# top_schem_rev3.net
KiCad netlist of a schematic drawn in Altium Designer
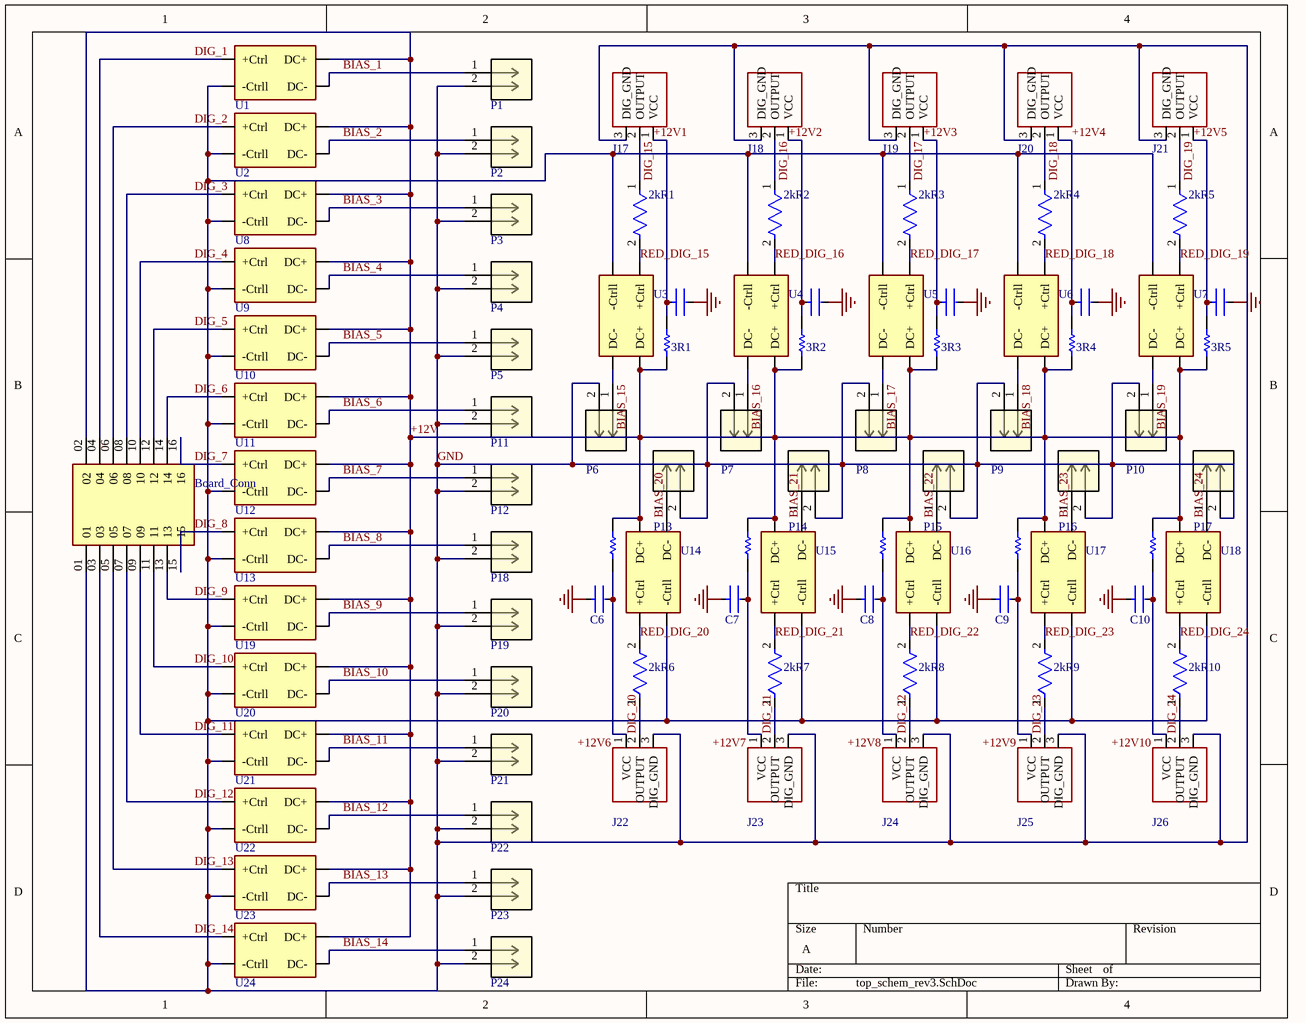
[diagram p0: top_schem_rev3.SchDoc]

(export (version "E")
  (design (tool "Eeschema 10.0.6"))
  (components
    (comp (ref "2kR1")
      (value "CRCW06031K80FKEA")
      (footprint "2kOhm")
      (description "Res Thick Film 0603 1.8K Ohm 1% 1/10W ±100ppm/°C Molded SMD Paper T/R")
      (fields (field (name "MANUFACTURER") "Vishay") (field (name "TOLERANCE") "1%"))
      (libsource (lib "ps_schlib") (part "CRCW06031K80FKEA"))
    )
    (comp (ref "2kR2")
      (value "CRCW06031K80FKEA")
      (footprint "2kOhm")
      (description "Res Thick Film 0603 1.8K Ohm 1% 1/10W ±100ppm/°C Molded SMD Paper T/R")
      (fields (field (name "MANUFACTURER") "Vishay") (field (name "TOLERANCE") "1%"))
      (libsource (lib "ps_schlib") (part "CRCW06031K80FKEA"))
    )
    (comp (ref "2kR3")
      (value "CRCW06031K80FKEA")
      (footprint "2kOhm")
      (description "Res Thick Film 0603 1.8K Ohm 1% 1/10W ±100ppm/°C Molded SMD Paper T/R")
      (fields (field (name "MANUFACTURER") "Vishay") (field (name "TOLERANCE") "1%"))
      (libsource (lib "ps_schlib") (part "CRCW06031K80FKEA"))
    )
    (comp (ref "2kR4")
      (value "CRCW06031K80FKEA")
      (footprint "2kOhm")
      (description "Res Thick Film 0603 1.8K Ohm 1% 1/10W ±100ppm/°C Molded SMD Paper T/R")
      (fields (field (name "MANUFACTURER") "Vishay") (field (name "TOLERANCE") "1%"))
      (libsource (lib "ps_schlib") (part "CRCW06031K80FKEA"))
    )
    (comp (ref "2kR5")
      (value "CRCW06031K80FKEA")
      (footprint "2kOhm")
      (description "Res Thick Film 0603 1.8K Ohm 1% 1/10W ±100ppm/°C Molded SMD Paper T/R")
      (fields (field (name "MANUFACTURER") "Vishay") (field (name "TOLERANCE") "1%"))
      (libsource (lib "ps_schlib") (part "CRCW06031K80FKEA"))
    )
    (comp (ref "2kR6")
      (value "CRCW06031K80FKEA")
      (footprint "2kOhm")
      (description "Res Thick Film 0603 1.8K Ohm 1% 1/10W ±100ppm/°C Molded SMD Paper T/R")
      (fields (field (name "MANUFACTURER") "Vishay") (field (name "TOLERANCE") "1%"))
      (libsource (lib "ps_schlib") (part "CRCW06031K80FKEA"))
    )
    (comp (ref "2kR7")
      (value "CRCW06031K80FKEA")
      (footprint "2kOhm")
      (description "Res Thick Film 0603 1.8K Ohm 1% 1/10W ±100ppm/°C Molded SMD Paper T/R")
      (fields (field (name "MANUFACTURER") "Vishay") (field (name "TOLERANCE") "1%"))
      (libsource (lib "ps_schlib") (part "CRCW06031K80FKEA"))
    )
    (comp (ref "2kR8")
      (value "CRCW06031K80FKEA")
      (footprint "2kOhm")
      (description "Res Thick Film 0603 1.8K Ohm 1% 1/10W ±100ppm/°C Molded SMD Paper T/R")
      (fields (field (name "MANUFACTURER") "Vishay") (field (name "TOLERANCE") "1%"))
      (libsource (lib "ps_schlib") (part "CRCW06031K80FKEA"))
    )
    (comp (ref "2kR9")
      (value "CRCW06031K80FKEA")
      (footprint "2kOhm")
      (description "Res Thick Film 0603 1.8K Ohm 1% 1/10W ±100ppm/°C Molded SMD Paper T/R")
      (fields (field (name "MANUFACTURER") "Vishay") (field (name "TOLERANCE") "1%"))
      (libsource (lib "ps_schlib") (part "CRCW06031K80FKEA"))
    )
    (comp (ref "2kR10")
      (value "CRCW06031K80FKEA")
      (footprint "2kOhm")
      (description "Res Thick Film 0603 1.8K Ohm 1% 1/10W ±100ppm/°C Molded SMD Paper T/R")
      (fields (field (name "MANUFACTURER") "Vishay") (field (name "TOLERANCE") "1%"))
      (libsource (lib "ps_schlib") (part "CRCW06031K80FKEA"))
    )
    (comp (ref "3R1")
      (value "ERJ-2BQJR30X")
      (footprint "03 Ohm")
      (description "RES 0.3 OHM 5% 1/6W 0402")
      (fields (field (name "MANUFACTURER") "Panasonic") (field (name "TOLERANCE") "5%"))
      (libsource (lib "ps_schlib") (part "ERJ-2BQJR30X"))
    )
    (comp (ref "3R2")
      (value "ERJ-2BQJR30X")
      (footprint "03 Ohm")
      (description "RES 0.3 OHM 5% 1/6W 0402")
      (fields (field (name "MANUFACTURER") "Panasonic") (field (name "TOLERANCE") "5%"))
      (libsource (lib "ps_schlib") (part "ERJ-2BQJR30X"))
    )
    (comp (ref "3R3")
      (value "ERJ-2BQJR30X")
      (footprint "03 Ohm")
      (description "RES 0.3 OHM 5% 1/6W 0402")
      (fields (field (name "MANUFACTURER") "Panasonic") (field (name "TOLERANCE") "5%"))
      (libsource (lib "ps_schlib") (part "ERJ-2BQJR30X"))
    )
    (comp (ref "3R4")
      (value "ERJ-2BQJR30X")
      (footprint "03 Ohm")
      (description "RES 0.3 OHM 5% 1/6W 0402")
      (fields (field (name "MANUFACTURER") "Panasonic") (field (name "TOLERANCE") "5%"))
      (libsource (lib "ps_schlib") (part "ERJ-2BQJR30X"))
    )
    (comp (ref "3R5")
      (value "ERJ-2BQJR30X")
      (footprint "03 Ohm")
      (description "RES 0.3 OHM 5% 1/6W 0402")
      (fields (field (name "MANUFACTURER") "Panasonic") (field (name "TOLERANCE") "5%"))
      (libsource (lib "ps_schlib") (part "ERJ-2BQJR30X"))
    )
    (comp (ref "3R6")
      (value "ERJ-2BQJR30X")
      (footprint "03 Ohm")
      (description "RES 0.3 OHM 5% 1/6W 0402")
      (fields (field (name "MANUFACTURER") "Panasonic") (field (name "TOLERANCE") "5%"))
      (libsource (lib "ps_schlib") (part "ERJ-2BQJR30X"))
    )
    (comp (ref "3R7")
      (value "ERJ-2BQJR30X")
      (footprint "03 Ohm")
      (description "RES 0.3 OHM 5% 1/6W 0402")
      (fields (field (name "MANUFACTURER") "Panasonic") (field (name "TOLERANCE") "5%"))
      (libsource (lib "ps_schlib") (part "ERJ-2BQJR30X"))
    )
    (comp (ref "3R8")
      (value "ERJ-2BQJR30X")
      (footprint "03 Ohm")
      (description "RES 0.3 OHM 5% 1/6W 0402")
      (fields (field (name "MANUFACTURER") "Panasonic") (field (name "TOLERANCE") "5%"))
      (libsource (lib "ps_schlib") (part "ERJ-2BQJR30X"))
    )
    (comp (ref "3R9")
      (value "ERJ-2BQJR30X")
      (footprint "03 Ohm")
      (description "RES 0.3 OHM 5% 1/6W 0402")
      (fields (field (name "MANUFACTURER") "Panasonic") (field (name "TOLERANCE") "5%"))
      (libsource (lib "ps_schlib") (part "ERJ-2BQJR30X"))
    )
    (comp (ref "3R10")
      (value "ERJ-2BQJR30X")
      (footprint "03 Ohm")
      (description "RES 0.3 OHM 5% 1/6W 0402")
      (fields (field (name "MANUFACTURER") "Panasonic") (field (name "TOLERANCE") "5%"))
      (libsource (lib "ps_schlib") (part "ERJ-2BQJR30X"))
    )
    (comp (ref "Board_Conn")
      (value "SSM-108-X-DV")
      (footprint "16 pin header")
      (libsource (lib "ps_schlib") (part "SSM-108-X-DV"))
    )
    (comp (ref "C1")
      (value "C0805C104K5RACTU")
      (footprint "100nF")
      (description "Cap Ceramic 0.1uF 50V X7R 10% SMD 2.0 x 1.2 mm 125 C Paper T/R")
      (fields (field (name "MANUFACTURER") "KEMET") (field (name "TOLERANCE") "10%"))
      (libsource (lib "ps_schlib") (part "C0805C104K5RACTU"))
    )
    (comp (ref "C2")
      (value "C0805C104K5RACTU")
      (footprint "100nF")
      (description "Cap Ceramic 0.1uF 50V X7R 10% SMD 2.0 x 1.2 mm 125 C Paper T/R")
      (fields (field (name "MANUFACTURER") "KEMET") (field (name "TOLERANCE") "10%"))
      (libsource (lib "ps_schlib") (part "C0805C104K5RACTU"))
    )
    (comp (ref "C3")
      (value "C0805C104K5RACTU")
      (footprint "100nF")
      (description "Cap Ceramic 0.1uF 50V X7R 10% SMD 2.0 x 1.2 mm 125 C Paper T/R")
      (fields (field (name "MANUFACTURER") "KEMET") (field (name "TOLERANCE") "10%"))
      (libsource (lib "ps_schlib") (part "C0805C104K5RACTU"))
    )
    (comp (ref "C4")
      (value "C0805C104K5RACTU")
      (footprint "100nF")
      (description "Cap Ceramic 0.1uF 50V X7R 10% SMD 2.0 x 1.2 mm 125 C Paper T/R")
      (fields (field (name "MANUFACTURER") "KEMET") (field (name "TOLERANCE") "10%"))
      (libsource (lib "ps_schlib") (part "C0805C104K5RACTU"))
    )
    (comp (ref "C5")
      (value "C0805C104K5RACTU")
      (footprint "100nF")
      (description "Cap Ceramic 0.1uF 50V X7R 10% SMD 2.0 x 1.2 mm 125 C Paper T/R")
      (fields (field (name "MANUFACTURER") "KEMET") (field (name "TOLERANCE") "10%"))
      (libsource (lib "ps_schlib") (part "C0805C104K5RACTU"))
    )
    (comp (ref "C6")
      (value "C0805C104K5RACTU")
      (footprint "100nF")
      (description "Cap Ceramic 0.1uF 50V X7R 10% SMD 2.0 x 1.2 mm 125 C Paper T/R")
      (fields (field (name "MANUFACTURER") "KEMET") (field (name "TOLERANCE") "10%"))
      (libsource (lib "ps_schlib") (part "C0805C104K5RACTU"))
    )
    (comp (ref "C7")
      (value "C0805C104K5RACTU")
      (footprint "100nF")
      (description "Cap Ceramic 0.1uF 50V X7R 10% SMD 2.0 x 1.2 mm 125 C Paper T/R")
      (fields (field (name "MANUFACTURER") "KEMET") (field (name "TOLERANCE") "10%"))
      (libsource (lib "ps_schlib") (part "C0805C104K5RACTU"))
    )
    (comp (ref "C8")
      (value "C0805C104K5RACTU")
      (footprint "100nF")
      (description "Cap Ceramic 0.1uF 50V X7R 10% SMD 2.0 x 1.2 mm 125 C Paper T/R")
      (fields (field (name "MANUFACTURER") "KEMET") (field (name "TOLERANCE") "10%"))
      (libsource (lib "ps_schlib") (part "C0805C104K5RACTU"))
    )
    (comp (ref "C9")
      (value "C0805C104K5RACTU")
      (footprint "100nF")
      (description "Cap Ceramic 0.1uF 50V X7R 10% SMD 2.0 x 1.2 mm 125 C Paper T/R")
      (fields (field (name "MANUFACTURER") "KEMET") (field (name "TOLERANCE") "10%"))
      (libsource (lib "ps_schlib") (part "C0805C104K5RACTU"))
    )
    (comp (ref "C10")
      (value "C0805C104K5RACTU")
      (footprint "100nF")
      (description "Cap Ceramic 0.1uF 50V X7R 10% SMD 2.0 x 1.2 mm 125 C Paper T/R")
      (fields (field (name "MANUFACTURER") "KEMET") (field (name "TOLERANCE") "10%"))
      (libsource (lib "ps_schlib") (part "C0805C104K5RACTU"))
    )
    (comp (ref "J17")
      (value "IF-D95T")
      (footprint "IF-D95")
      (description "DETECTOR PHOTOLOGIC TTL/CMOS")
      (fields (field (name "MANUFACTURER") "Industrial Fiber Optics"))
      (libsource (lib "ps_schlib") (part "IF-D95T"))
    )
    (comp (ref "J18")
      (value "IF-D95T")
      (footprint "IF-D95")
      (description "DETECTOR PHOTOLOGIC TTL/CMOS")
      (fields (field (name "MANUFACTURER") "Industrial Fiber Optics"))
      (libsource (lib "ps_schlib") (part "IF-D95T"))
    )
    (comp (ref "J19")
      (value "IF-D95T")
      (footprint "IF-D95")
      (description "DETECTOR PHOTOLOGIC TTL/CMOS")
      (fields (field (name "MANUFACTURER") "Industrial Fiber Optics"))
      (libsource (lib "ps_schlib") (part "IF-D95T"))
    )
    (comp (ref "J20")
      (value "IF-D95T")
      (footprint "IF-D95")
      (description "DETECTOR PHOTOLOGIC TTL/CMOS")
      (fields (field (name "MANUFACTURER") "Industrial Fiber Optics"))
      (libsource (lib "ps_schlib") (part "IF-D95T"))
    )
    (comp (ref "J21")
      (value "IF-D95T")
      (footprint "IF-D95")
      (description "DETECTOR PHOTOLOGIC TTL/CMOS")
      (fields (field (name "MANUFACTURER") "Industrial Fiber Optics"))
      (libsource (lib "ps_schlib") (part "IF-D95T"))
    )
    (comp (ref "J22")
      (value "IF-D95T")
      (footprint "IF-D95")
      (description "DETECTOR PHOTOLOGIC TTL/CMOS")
      (fields (field (name "MANUFACTURER") "Industrial Fiber Optics"))
      (libsource (lib "ps_schlib") (part "IF-D95T"))
    )
    (comp (ref "J23")
      (value "IF-D95T")
      (footprint "IF-D95")
      (description "DETECTOR PHOTOLOGIC TTL/CMOS")
      (fields (field (name "MANUFACTURER") "Industrial Fiber Optics"))
      (libsource (lib "ps_schlib") (part "IF-D95T"))
    )
    (comp (ref "J24")
      (value "IF-D95T")
      (footprint "IF-D95")
      (description "DETECTOR PHOTOLOGIC TTL/CMOS")
      (fields (field (name "MANUFACTURER") "Industrial Fiber Optics"))
      (libsource (lib "ps_schlib") (part "IF-D95T"))
    )
    (comp (ref "J25")
      (value "IF-D95T")
      (footprint "IF-D95")
      (description "DETECTOR PHOTOLOGIC TTL/CMOS")
      (fields (field (name "MANUFACTURER") "Industrial Fiber Optics"))
      (libsource (lib "ps_schlib") (part "IF-D95T"))
    )
    (comp (ref "J26")
      (value "IF-D95T")
      (footprint "IF-D95")
      (description "DETECTOR PHOTOLOGIC TTL/CMOS")
      (fields (field (name "MANUFACTURER") "Industrial Fiber Optics"))
      (libsource (lib "ps_schlib") (part "IF-D95T"))
    )
    (comp (ref "P1")
      (value "1054311102")
      (footprint "CONN_1054311102_MOL")
      (fields (field (name "MANUFACTURER") "Molex"))
      (libsource (lib "ps_schlib") (part "1054311102"))
    )
    (comp (ref "P2")
      (value "1054311102")
      (footprint "CONN_1054311102_MOL")
      (fields (field (name "MANUFACTURER") "Molex"))
      (libsource (lib "ps_schlib") (part "1054311102"))
    )
    (comp (ref "P3")
      (value "1054311102")
      (footprint "CONN_1054311102_MOL")
      (fields (field (name "MANUFACTURER") "Molex"))
      (libsource (lib "ps_schlib") (part "1054311102"))
    )
    (comp (ref "P4")
      (value "1054311102")
      (footprint "CONN_1054311102_MOL")
      (fields (field (name "MANUFACTURER") "Molex"))
      (libsource (lib "ps_schlib") (part "1054311102"))
    )
    (comp (ref "P5")
      (value "1054311102")
      (footprint "CONN_1054311102_MOL")
      (fields (field (name "MANUFACTURER") "Molex"))
      (libsource (lib "ps_schlib") (part "1054311102"))
    )
    (comp (ref "P6")
      (value "1054311102")
      (footprint "CONN_1054311102_MOL")
      (fields (field (name "MANUFACTURER") "Molex"))
      (libsource (lib "") (part "1054311102_2"))
    )
    (comp (ref "P7")
      (value "1054311102")
      (footprint "CONN_1054311102_MOL")
      (fields (field (name "MANUFACTURER") "Molex"))
      (libsource (lib "") (part "1054311102_2"))
    )
    (comp (ref "P8")
      (value "1054311102")
      (footprint "CONN_1054311102_MOL")
      (fields (field (name "MANUFACTURER") "Molex"))
      (libsource (lib "") (part "1054311102_2"))
    )
    (comp (ref "P9")
      (value "1054311102")
      (footprint "CONN_1054311102_MOL")
      (fields (field (name "MANUFACTURER") "Molex"))
      (libsource (lib "") (part "1054311102_2"))
    )
    (comp (ref "P10")
      (value "1054311102")
      (footprint "CONN_1054311102_MOL")
      (fields (field (name "MANUFACTURER") "Molex"))
      (libsource (lib "") (part "1054311102_2"))
    )
    (comp (ref "P11")
      (value "1054311102")
      (footprint "CONN_1054311102_MOL")
      (fields (field (name "MANUFACTURER") "Molex"))
      (libsource (lib "ps_schlib") (part "1054311102"))
    )
    (comp (ref "P12")
      (value "1054311102")
      (footprint "CONN_1054311102_MOL")
      (fields (field (name "MANUFACTURER") "Molex"))
      (libsource (lib "ps_schlib") (part "1054311102"))
    )
    (comp (ref "P13")
      (value "1054311102")
      (footprint "CONN_1054311102_MOL")
      (fields (field (name "MANUFACTURER") "Molex"))
      (libsource (lib "") (part "1054311102_1"))
    )
    (comp (ref "P14")
      (value "1054311102")
      (footprint "CONN_1054311102_MOL")
      (fields (field (name "MANUFACTURER") "Molex"))
      (libsource (lib "") (part "1054311102_1"))
    )
    (comp (ref "P15")
      (value "1054311102")
      (footprint "CONN_1054311102_MOL")
      (fields (field (name "MANUFACTURER") "Molex"))
      (libsource (lib "") (part "1054311102_1"))
    )
    (comp (ref "P16")
      (value "1054311102")
      (footprint "CONN_1054311102_MOL")
      (fields (field (name "MANUFACTURER") "Molex"))
      (libsource (lib "") (part "1054311102_1"))
    )
    (comp (ref "P17")
      (value "1054311102")
      (footprint "CONN_1054311102_MOL")
      (fields (field (name "MANUFACTURER") "Molex"))
      (libsource (lib "") (part "1054311102_1"))
    )
    (comp (ref "P18")
      (value "1054311102")
      (footprint "CONN_1054311102_MOL")
      (fields (field (name "MANUFACTURER") "Molex"))
      (libsource (lib "ps_schlib") (part "1054311102"))
    )
    (comp (ref "P19")
      (value "1054311102")
      (footprint "CONN_1054311102_MOL")
      (fields (field (name "MANUFACTURER") "Molex"))
      (libsource (lib "ps_schlib") (part "1054311102"))
    )
    (comp (ref "P20")
      (value "1054311102")
      (footprint "CONN_1054311102_MOL")
      (fields (field (name "MANUFACTURER") "Molex"))
      (libsource (lib "ps_schlib") (part "1054311102"))
    )
    (comp (ref "P21")
      (value "1054311102")
      (footprint "CONN_1054311102_MOL")
      (fields (field (name "MANUFACTURER") "Molex"))
      (libsource (lib "ps_schlib") (part "1054311102"))
    )
    (comp (ref "P22")
      (value "1054311102")
      (footprint "CONN_1054311102_MOL")
      (fields (field (name "MANUFACTURER") "Molex"))
      (libsource (lib "ps_schlib") (part "1054311102"))
    )
    (comp (ref "P23")
      (value "1054311102")
      (footprint "CONN_1054311102_MOL")
      (fields (field (name "MANUFACTURER") "Molex"))
      (libsource (lib "ps_schlib") (part "1054311102"))
    )
    (comp (ref "P24")
      (value "1054311102")
      (footprint "CONN_1054311102_MOL")
      (fields (field (name "MANUFACTURER") "Molex"))
      (libsource (lib "ps_schlib") (part "1054311102"))
    )
    (comp (ref "U1")
      (value "Solid state relay")
      (footprint "CPC1002N")
      (libsource (lib "ps_schlib") (part "CPC1002N"))
    )
    (comp (ref "U2")
      (value "Solid state relay")
      (footprint "CPC1002N")
      (libsource (lib "ps_schlib") (part "CPC1002N"))
    )
    (comp (ref "U3")
      (value "Solid state relay")
      (footprint "CPC1002N")
      (libsource (lib "") (part "CPC1002N_1"))
    )
    (comp (ref "U4")
      (value "Solid state relay")
      (footprint "CPC1002N")
      (libsource (lib "") (part "CPC1002N_1"))
    )
    (comp (ref "U5")
      (value "Solid state relay")
      (footprint "CPC1002N")
      (libsource (lib "") (part "CPC1002N_1"))
    )
    (comp (ref "U6")
      (value "Solid state relay")
      (footprint "CPC1002N")
      (libsource (lib "") (part "CPC1002N_1"))
    )
    (comp (ref "U7")
      (value "Solid state relay")
      (footprint "CPC1002N")
      (libsource (lib "") (part "CPC1002N_1"))
    )
    (comp (ref "U8")
      (value "Solid state relay")
      (footprint "CPC1002N")
      (libsource (lib "ps_schlib") (part "CPC1002N"))
    )
    (comp (ref "U9")
      (value "Solid state relay")
      (footprint "CPC1002N")
      (libsource (lib "ps_schlib") (part "CPC1002N"))
    )
    (comp (ref "U10")
      (value "Solid state relay")
      (footprint "CPC1002N")
      (libsource (lib "ps_schlib") (part "CPC1002N"))
    )
    (comp (ref "U11")
      (value "Solid state relay")
      (footprint "CPC1002N")
      (libsource (lib "ps_schlib") (part "CPC1002N"))
    )
    (comp (ref "U12")
      (value "Solid state relay")
      (footprint "CPC1002N")
      (libsource (lib "ps_schlib") (part "CPC1002N"))
    )
    (comp (ref "U13")
      (value "Solid state relay")
      (footprint "CPC1002N")
      (libsource (lib "ps_schlib") (part "CPC1002N"))
    )
    (comp (ref "U14")
      (value "Solid state relay")
      (footprint "CPC1002N")
      (libsource (lib "") (part "CPC1002N_2"))
    )
    (comp (ref "U15")
      (value "Solid state relay")
      (footprint "CPC1002N")
      (libsource (lib "") (part "CPC1002N_2"))
    )
    (comp (ref "U16")
      (value "Solid state relay")
      (footprint "CPC1002N")
      (libsource (lib "") (part "CPC1002N_2"))
    )
    (comp (ref "U17")
      (value "Solid state relay")
      (footprint "CPC1002N")
      (libsource (lib "") (part "CPC1002N_2"))
    )
    (comp (ref "U18")
      (value "Solid state relay")
      (footprint "CPC1002N")
      (libsource (lib "") (part "CPC1002N_2"))
    )
    (comp (ref "U19")
      (value "Solid state relay")
      (footprint "CPC1002N")
      (libsource (lib "ps_schlib") (part "CPC1002N"))
    )
    (comp (ref "U20")
      (value "Solid state relay")
      (footprint "CPC1002N")
      (libsource (lib "ps_schlib") (part "CPC1002N"))
    )
    (comp (ref "U21")
      (value "Solid state relay")
      (footprint "CPC1002N")
      (libsource (lib "ps_schlib") (part "CPC1002N"))
    )
    (comp (ref "U22")
      (value "Solid state relay")
      (footprint "CPC1002N")
      (libsource (lib "ps_schlib") (part "CPC1002N"))
    )
    (comp (ref "U23")
      (value "Solid state relay")
      (footprint "CPC1002N")
      (libsource (lib "ps_schlib") (part "CPC1002N"))
    )
    (comp (ref "U24")
      (value "Solid state relay")
      (footprint "CPC1002N")
      (libsource (lib "ps_schlib") (part "CPC1002N"))
    )
  )
  (nets
    (net (code "1") (name "/+12V") (class "Default")
      (node (ref "3R1") (pin "1") (pinfunction "1_1") (pintype "passive"))
      (node (ref "3R10") (pin "2") (pinfunction "2_2") (pintype "passive"))
      (node (ref "3R2") (pin "1") (pinfunction "1_1") (pintype "passive"))
      (node (ref "3R3") (pin "1") (pinfunction "1_1") (pintype "passive"))
      (node (ref "3R4") (pin "1") (pinfunction "1_1") (pintype "passive"))
      (node (ref "3R5") (pin "1") (pinfunction "1_1") (pintype "passive"))
      (node (ref "3R6") (pin "2") (pinfunction "2_2") (pintype "passive"))
      (node (ref "3R7") (pin "2") (pinfunction "2_2") (pintype "passive"))
      (node (ref "3R8") (pin "2") (pinfunction "2_2") (pintype "passive"))
      (node (ref "3R9") (pin "2") (pinfunction "2_2") (pintype "passive"))
      (node (ref "Board_Conn") (pin "02") (pinfunction "02_02") (pintype "passive"))
      (node (ref "U1") (pin "4") (pinfunction "DC+_4") (pintype "passive"))
      (node (ref "U10") (pin "4") (pinfunction "DC+_4") (pintype "passive"))
      (node (ref "U11") (pin "4") (pinfunction "DC+_4") (pintype "passive"))
      (node (ref "U12") (pin "4") (pinfunction "DC+_4") (pintype "passive"))
      (node (ref "U13") (pin "4") (pinfunction "DC+_4") (pintype "passive"))
      (node (ref "U14") (pin "4") (pinfunction "DC+_4") (pintype "passive"))
      (node (ref "U15") (pin "4") (pinfunction "DC+_4") (pintype "passive"))
      (node (ref "U16") (pin "4") (pinfunction "DC+_4") (pintype "passive"))
      (node (ref "U17") (pin "4") (pinfunction "DC+_4") (pintype "passive"))
      (node (ref "U18") (pin "4") (pinfunction "DC+_4") (pintype "passive"))
      (node (ref "U19") (pin "4") (pinfunction "DC+_4") (pintype "passive"))
      (node (ref "U2") (pin "4") (pinfunction "DC+_4") (pintype "passive"))
      (node (ref "U20") (pin "4") (pinfunction "DC+_4") (pintype "passive"))
      (node (ref "U21") (pin "4") (pinfunction "DC+_4") (pintype "passive"))
      (node (ref "U22") (pin "4") (pinfunction "DC+_4") (pintype "passive"))
      (node (ref "U23") (pin "4") (pinfunction "DC+_4") (pintype "passive"))
      (node (ref "U24") (pin "4") (pinfunction "DC+_4") (pintype "passive"))
      (node (ref "U3") (pin "4") (pinfunction "DC+_4") (pintype "passive"))
      (node (ref "U4") (pin "4") (pinfunction "DC+_4") (pintype "passive"))
      (node (ref "U5") (pin "4") (pinfunction "DC+_4") (pintype "passive"))
      (node (ref "U6") (pin "4") (pinfunction "DC+_4") (pintype "passive"))
      (node (ref "U7") (pin "4") (pinfunction "DC+_4") (pintype "passive"))
      (node (ref "U8") (pin "4") (pinfunction "DC+_4") (pintype "passive"))
      (node (ref "U9") (pin "4") (pinfunction "DC+_4") (pintype "passive"))
    )
    (net (code "2") (name "/+12V1") (class "Default")
      (node (ref "3R1") (pin "2") (pinfunction "2_2") (pintype "passive"))
      (node (ref "C1") (pin "1") (pinfunction "1_1") (pintype "passive"))
      (node (ref "J17") (pin "1") (pinfunction "VCC_1") (pintype "passive"))
    )
    (net (code "3") (name "/+12V2") (class "Default")
      (node (ref "3R2") (pin "2") (pinfunction "2_2") (pintype "passive"))
      (node (ref "C2") (pin "1") (pinfunction "1_1") (pintype "passive"))
      (node (ref "J18") (pin "1") (pinfunction "VCC_1") (pintype "passive"))
    )
    (net (code "4") (name "/+12V3") (class "Default")
      (node (ref "3R3") (pin "2") (pinfunction "2_2") (pintype "passive"))
      (node (ref "C3") (pin "1") (pinfunction "1_1") (pintype "passive"))
      (node (ref "J19") (pin "1") (pinfunction "VCC_1") (pintype "passive"))
    )
    (net (code "5") (name "/+12V4") (class "Default")
      (node (ref "3R4") (pin "2") (pinfunction "2_2") (pintype "passive"))
      (node (ref "C4") (pin "1") (pinfunction "1_1") (pintype "passive"))
      (node (ref "J20") (pin "1") (pinfunction "VCC_1") (pintype "passive"))
    )
    (net (code "6") (name "/+12V5") (class "Default")
      (node (ref "3R5") (pin "2") (pinfunction "2_2") (pintype "passive"))
      (node (ref "C5") (pin "1") (pinfunction "1_1") (pintype "passive"))
      (node (ref "J21") (pin "1") (pinfunction "VCC_1") (pintype "passive"))
    )
    (net (code "7") (name "/+12V6") (class "Default")
      (node (ref "3R6") (pin "1") (pinfunction "1_1") (pintype "passive"))
      (node (ref "C6") (pin "2") (pinfunction "2_2") (pintype "passive"))
      (node (ref "J22") (pin "1") (pinfunction "VCC_1") (pintype "passive"))
    )
    (net (code "8") (name "/+12V7") (class "Default")
      (node (ref "3R7") (pin "1") (pinfunction "1_1") (pintype "passive"))
      (node (ref "C7") (pin "2") (pinfunction "2_2") (pintype "passive"))
      (node (ref "J23") (pin "1") (pinfunction "VCC_1") (pintype "passive"))
    )
    (net (code "9") (name "/+12V8") (class "Default")
      (node (ref "3R8") (pin "1") (pinfunction "1_1") (pintype "passive"))
      (node (ref "C8") (pin "2") (pinfunction "2_2") (pintype "passive"))
      (node (ref "J24") (pin "1") (pinfunction "VCC_1") (pintype "passive"))
    )
    (net (code "10") (name "/+12V9") (class "Default")
      (node (ref "3R9") (pin "1") (pinfunction "1_1") (pintype "passive"))
      (node (ref "C9") (pin "2") (pinfunction "2_2") (pintype "passive"))
      (node (ref "J25") (pin "1") (pinfunction "VCC_1") (pintype "passive"))
    )
    (net (code "11") (name "/+12V10") (class "Default")
      (node (ref "3R10") (pin "1") (pinfunction "1_1") (pintype "passive"))
      (node (ref "C10") (pin "2") (pinfunction "2_2") (pintype "passive"))
      (node (ref "J26") (pin "1") (pinfunction "VCC_1") (pintype "passive"))
    )
    (net (code "12") (name "/BIAS_1") (class "Default")
      (node (ref "P1") (pin "1") (pinfunction "1_1") (pintype "passive"))
      (node (ref "U1") (pin "3") (pinfunction "DC-_3") (pintype "passive"))
    )
    (net (code "13") (name "/BIAS_2") (class "Default")
      (node (ref "P2") (pin "1") (pinfunction "1_1") (pintype "passive"))
      (node (ref "U2") (pin "3") (pinfunction "DC-_3") (pintype "passive"))
    )
    (net (code "14") (name "/BIAS_3") (class "Default")
      (node (ref "P3") (pin "1") (pinfunction "1_1") (pintype "passive"))
      (node (ref "U8") (pin "3") (pinfunction "DC-_3") (pintype "passive"))
    )
    (net (code "15") (name "/BIAS_4") (class "Default")
      (node (ref "P4") (pin "1") (pinfunction "1_1") (pintype "passive"))
      (node (ref "U9") (pin "3") (pinfunction "DC-_3") (pintype "passive"))
    )
    (net (code "16") (name "/BIAS_5") (class "Default")
      (node (ref "P5") (pin "1") (pinfunction "1_1") (pintype "passive"))
      (node (ref "U10") (pin "3") (pinfunction "DC-_3") (pintype "passive"))
    )
    (net (code "17") (name "/BIAS_6") (class "Default")
      (node (ref "P11") (pin "1") (pinfunction "1_1") (pintype "passive"))
      (node (ref "U11") (pin "3") (pinfunction "DC-_3") (pintype "passive"))
    )
    (net (code "18") (name "/BIAS_7") (class "Default")
      (node (ref "P12") (pin "1") (pinfunction "1_1") (pintype "passive"))
      (node (ref "U12") (pin "3") (pinfunction "DC-_3") (pintype "passive"))
    )
    (net (code "19") (name "/BIAS_8") (class "Default")
      (node (ref "P18") (pin "1") (pinfunction "1_1") (pintype "passive"))
      (node (ref "U13") (pin "3") (pinfunction "DC-_3") (pintype "passive"))
    )
    (net (code "20") (name "/BIAS_9") (class "Default")
      (node (ref "P19") (pin "1") (pinfunction "1_1") (pintype "passive"))
      (node (ref "U19") (pin "3") (pinfunction "DC-_3") (pintype "passive"))
    )
    (net (code "21") (name "/BIAS_10") (class "Default")
      (node (ref "P20") (pin "1") (pinfunction "1_1") (pintype "passive"))
      (node (ref "U20") (pin "3") (pinfunction "DC-_3") (pintype "passive"))
    )
    (net (code "22") (name "/BIAS_11") (class "Default")
      (node (ref "P21") (pin "1") (pinfunction "1_1") (pintype "passive"))
      (node (ref "U21") (pin "3") (pinfunction "DC-_3") (pintype "passive"))
    )
    (net (code "23") (name "/BIAS_12") (class "Default")
      (node (ref "P22") (pin "1") (pinfunction "1_1") (pintype "passive"))
      (node (ref "U22") (pin "3") (pinfunction "DC-_3") (pintype "passive"))
    )
    (net (code "24") (name "/BIAS_13") (class "Default")
      (node (ref "P23") (pin "1") (pinfunction "1_1") (pintype "passive"))
      (node (ref "U23") (pin "3") (pinfunction "DC-_3") (pintype "passive"))
    )
    (net (code "25") (name "/BIAS_14") (class "Default")
      (node (ref "P24") (pin "1") (pinfunction "1_1") (pintype "passive"))
      (node (ref "U24") (pin "3") (pinfunction "DC-_3") (pintype "passive"))
    )
    (net (code "26") (name "/BIAS_15") (class "Default")
      (node (ref "P6") (pin "1") (pinfunction "1_1") (pintype "passive"))
      (node (ref "U3") (pin "3") (pinfunction "DC-_3") (pintype "passive"))
    )
    (net (code "27") (name "/BIAS_16") (class "Default")
      (node (ref "P7") (pin "1") (pinfunction "1_1") (pintype "passive"))
      (node (ref "U4") (pin "3") (pinfunction "DC-_3") (pintype "passive"))
    )
    (net (code "28") (name "/BIAS_17") (class "Default")
      (node (ref "P8") (pin "1") (pinfunction "1_1") (pintype "passive"))
      (node (ref "U5") (pin "3") (pinfunction "DC-_3") (pintype "passive"))
    )
    (net (code "29") (name "/BIAS_18") (class "Default")
      (node (ref "P9") (pin "1") (pinfunction "1_1") (pintype "passive"))
      (node (ref "U6") (pin "3") (pinfunction "DC-_3") (pintype "passive"))
    )
    (net (code "30") (name "/BIAS_19") (class "Default")
      (node (ref "P10") (pin "1") (pinfunction "1_1") (pintype "passive"))
      (node (ref "U7") (pin "3") (pinfunction "DC-_3") (pintype "passive"))
    )
    (net (code "31") (name "/BIAS_20") (class "Default")
      (node (ref "P13") (pin "1") (pinfunction "1_1") (pintype "passive"))
      (node (ref "U14") (pin "3") (pinfunction "DC-_3") (pintype "passive"))
    )
    (net (code "32") (name "/BIAS_21") (class "Default")
      (node (ref "P14") (pin "1") (pinfunction "1_1") (pintype "passive"))
      (node (ref "U15") (pin "3") (pinfunction "DC-_3") (pintype "passive"))
    )
    (net (code "33") (name "/BIAS_22") (class "Default")
      (node (ref "P15") (pin "1") (pinfunction "1_1") (pintype "passive"))
      (node (ref "U16") (pin "3") (pinfunction "DC-_3") (pintype "passive"))
    )
    (net (code "34") (name "/BIAS_23") (class "Default")
      (node (ref "P16") (pin "1") (pinfunction "1_1") (pintype "passive"))
      (node (ref "U17") (pin "3") (pinfunction "DC-_3") (pintype "passive"))
    )
    (net (code "35") (name "/BIAS_24") (class "Default")
      (node (ref "P17") (pin "1") (pinfunction "1_1") (pintype "passive"))
      (node (ref "U18") (pin "3") (pinfunction "DC-_3") (pintype "passive"))
    )
    (net (code "36") (name "/DIG_1") (class "Default")
      (node (ref "Board_Conn") (pin "04") (pinfunction "04_04") (pintype "passive"))
      (node (ref "U1") (pin "1") (pinfunction "+Ctrl_1") (pintype "passive"))
    )
    (net (code "37") (name "/DIG_2") (class "Default")
      (node (ref "Board_Conn") (pin "06") (pinfunction "06_06") (pintype "passive"))
      (node (ref "U2") (pin "1") (pinfunction "+Ctrl_1") (pintype "passive"))
    )
    (net (code "38") (name "/DIG_3") (class "Default")
      (node (ref "Board_Conn") (pin "08") (pinfunction "08_08") (pintype "passive"))
      (node (ref "U8") (pin "1") (pinfunction "+Ctrl_1") (pintype "passive"))
    )
    (net (code "39") (name "/DIG_4") (class "Default")
      (node (ref "Board_Conn") (pin "10") (pinfunction "10_10") (pintype "passive"))
      (node (ref "U9") (pin "1") (pinfunction "+Ctrl_1") (pintype "passive"))
    )
    (net (code "40") (name "/DIG_5") (class "Default")
      (node (ref "Board_Conn") (pin "12") (pinfunction "12_12") (pintype "passive"))
      (node (ref "U10") (pin "1") (pinfunction "+Ctrl_1") (pintype "passive"))
    )
    (net (code "41") (name "/DIG_6") (class "Default")
      (node (ref "Board_Conn") (pin "14") (pinfunction "14_14") (pintype "passive"))
      (node (ref "U11") (pin "1") (pinfunction "+Ctrl_1") (pintype "passive"))
    )
    (net (code "42") (name "/DIG_7") (class "Default")
      (node (ref "Board_Conn") (pin "16") (pinfunction "16_16") (pintype "passive"))
      (node (ref "U12") (pin "1") (pinfunction "+Ctrl_1") (pintype "passive"))
    )
    (net (code "43") (name "/DIG_8") (class "Default")
      (node (ref "Board_Conn") (pin "15") (pinfunction "15_15") (pintype "passive"))
      (node (ref "U13") (pin "1") (pinfunction "+Ctrl_1") (pintype "passive"))
    )
    (net (code "44") (name "/DIG_9") (class "Default")
      (node (ref "Board_Conn") (pin "13") (pinfunction "13_13") (pintype "passive"))
      (node (ref "U19") (pin "1") (pinfunction "+Ctrl_1") (pintype "passive"))
    )
    (net (code "45") (name "/DIG_10") (class "Default")
      (node (ref "Board_Conn") (pin "11") (pinfunction "11_11") (pintype "passive"))
      (node (ref "U20") (pin "1") (pinfunction "+Ctrl_1") (pintype "passive"))
    )
    (net (code "46") (name "/DIG_11") (class "Default")
      (node (ref "Board_Conn") (pin "09") (pinfunction "09_09") (pintype "passive"))
      (node (ref "U21") (pin "1") (pinfunction "+Ctrl_1") (pintype "passive"))
    )
    (net (code "47") (name "/DIG_12") (class "Default")
      (node (ref "Board_Conn") (pin "07") (pinfunction "07_07") (pintype "passive"))
      (node (ref "U22") (pin "1") (pinfunction "+Ctrl_1") (pintype "passive"))
    )
    (net (code "48") (name "/DIG_13") (class "Default")
      (node (ref "Board_Conn") (pin "05") (pinfunction "05_05") (pintype "passive"))
      (node (ref "U23") (pin "1") (pinfunction "+Ctrl_1") (pintype "passive"))
    )
    (net (code "49") (name "/DIG_14") (class "Default")
      (node (ref "Board_Conn") (pin "03") (pinfunction "03_03") (pintype "passive"))
      (node (ref "U24") (pin "1") (pinfunction "+Ctrl_1") (pintype "passive"))
    )
    (net (code "50") (name "/DIG_15") (class "Default")
      (node (ref "2kR1") (pin "1") (pinfunction "1_1") (pintype "passive"))
      (node (ref "J17") (pin "2") (pinfunction "OUTPUT_2") (pintype "passive"))
    )
    (net (code "51") (name "/DIG_16") (class "Default")
      (node (ref "2kR2") (pin "1") (pinfunction "1_1") (pintype "passive"))
      (node (ref "J18") (pin "2") (pinfunction "OUTPUT_2") (pintype "passive"))
    )
    (net (code "52") (name "/DIG_17") (class "Default")
      (node (ref "2kR3") (pin "1") (pinfunction "1_1") (pintype "passive"))
      (node (ref "J19") (pin "2") (pinfunction "OUTPUT_2") (pintype "passive"))
    )
    (net (code "53") (name "/DIG_18") (class "Default")
      (node (ref "2kR4") (pin "1") (pinfunction "1_1") (pintype "passive"))
      (node (ref "J20") (pin "2") (pinfunction "OUTPUT_2") (pintype "passive"))
    )
    (net (code "54") (name "/DIG_19") (class "Default")
      (node (ref "2kR5") (pin "1") (pinfunction "1_1") (pintype "passive"))
      (node (ref "J21") (pin "2") (pinfunction "OUTPUT_2") (pintype "passive"))
    )
    (net (code "55") (name "/DIG_20") (class "Default")
      (node (ref "2kR6") (pin "1") (pinfunction "1_1") (pintype "passive"))
      (node (ref "J22") (pin "2") (pinfunction "OUTPUT_2") (pintype "passive"))
    )
    (net (code "56") (name "/DIG_21") (class "Default")
      (node (ref "2kR7") (pin "1") (pinfunction "1_1") (pintype "passive"))
      (node (ref "J23") (pin "2") (pinfunction "OUTPUT_2") (pintype "passive"))
    )
    (net (code "57") (name "/DIG_22") (class "Default")
      (node (ref "2kR8") (pin "1") (pinfunction "1_1") (pintype "passive"))
      (node (ref "J24") (pin "2") (pinfunction "OUTPUT_2") (pintype "passive"))
    )
    (net (code "58") (name "/DIG_23") (class "Default")
      (node (ref "2kR9") (pin "1") (pinfunction "1_1") (pintype "passive"))
      (node (ref "J25") (pin "2") (pinfunction "OUTPUT_2") (pintype "passive"))
    )
    (net (code "59") (name "/DIG_24") (class "Default")
      (node (ref "2kR10") (pin "1") (pinfunction "1_1") (pintype "passive"))
      (node (ref "J26") (pin "2") (pinfunction "OUTPUT_2") (pintype "passive"))
    )
    (net (code "60") (name "/RED_DIG_15") (class "Default")
      (node (ref "2kR1") (pin "2") (pinfunction "2_2") (pintype "passive"))
      (node (ref "U3") (pin "1") (pinfunction "+Ctrl_1") (pintype "passive"))
    )
    (net (code "61") (name "/RED_DIG_16") (class "Default")
      (node (ref "2kR2") (pin "2") (pinfunction "2_2") (pintype "passive"))
      (node (ref "U4") (pin "1") (pinfunction "+Ctrl_1") (pintype "passive"))
    )
    (net (code "62") (name "/RED_DIG_17") (class "Default")
      (node (ref "2kR3") (pin "2") (pinfunction "2_2") (pintype "passive"))
      (node (ref "U5") (pin "1") (pinfunction "+Ctrl_1") (pintype "passive"))
    )
    (net (code "63") (name "/RED_DIG_18") (class "Default")
      (node (ref "2kR4") (pin "2") (pinfunction "2_2") (pintype "passive"))
      (node (ref "U6") (pin "1") (pinfunction "+Ctrl_1") (pintype "passive"))
    )
    (net (code "64") (name "/RED_DIG_19") (class "Default")
      (node (ref "2kR5") (pin "2") (pinfunction "2_2") (pintype "passive"))
      (node (ref "U7") (pin "1") (pinfunction "+Ctrl_1") (pintype "passive"))
    )
    (net (code "65") (name "/RED_DIG_20") (class "Default")
      (node (ref "2kR6") (pin "2") (pinfunction "2_2") (pintype "passive"))
      (node (ref "U14") (pin "1") (pinfunction "+Ctrl_1") (pintype "passive"))
    )
    (net (code "66") (name "/RED_DIG_21") (class "Default")
      (node (ref "2kR7") (pin "2") (pinfunction "2_2") (pintype "passive"))
      (node (ref "U15") (pin "1") (pinfunction "+Ctrl_1") (pintype "passive"))
    )
    (net (code "67") (name "/RED_DIG_22") (class "Default")
      (node (ref "2kR8") (pin "2") (pinfunction "2_2") (pintype "passive"))
      (node (ref "U16") (pin "1") (pinfunction "+Ctrl_1") (pintype "passive"))
    )
    (net (code "68") (name "/RED_DIG_23") (class "Default")
      (node (ref "2kR9") (pin "2") (pinfunction "2_2") (pintype "passive"))
      (node (ref "U17") (pin "1") (pinfunction "+Ctrl_1") (pintype "passive"))
    )
    (net (code "69") (name "/RED_DIG_24") (class "Default")
      (node (ref "2kR10") (pin "2") (pinfunction "2_2") (pintype "passive"))
      (node (ref "U18") (pin "1") (pinfunction "+Ctrl_1") (pintype "passive"))
    )
    (net (code "70") (name "GND") (class "Default")
      (node (ref "Board_Conn") (pin "01") (pinfunction "01_01") (pintype "passive"))
      (node (ref "C1") (pin "2") (pinfunction "2_2") (pintype "passive"))
      (node (ref "C10") (pin "1") (pinfunction "1_1") (pintype "passive"))
      (node (ref "C2") (pin "2") (pinfunction "2_2") (pintype "passive"))
      (node (ref "C3") (pin "2") (pinfunction "2_2") (pintype "passive"))
      (node (ref "C4") (pin "2") (pinfunction "2_2") (pintype "passive"))
      (node (ref "C5") (pin "2") (pinfunction "2_2") (pintype "passive"))
      (node (ref "C6") (pin "1") (pinfunction "1_1") (pintype "passive"))
      (node (ref "C7") (pin "1") (pinfunction "1_1") (pintype "passive"))
      (node (ref "C8") (pin "1") (pinfunction "1_1") (pintype "passive"))
      (node (ref "C9") (pin "1") (pinfunction "1_1") (pintype "passive"))
      (node (ref "J17") (pin "3") (pinfunction "DIG_GND_3") (pintype "passive"))
      (node (ref "J18") (pin "3") (pinfunction "DIG_GND_3") (pintype "passive"))
      (node (ref "J19") (pin "3") (pinfunction "DIG_GND_3") (pintype "passive"))
      (node (ref "J20") (pin "3") (pinfunction "DIG_GND_3") (pintype "passive"))
      (node (ref "J21") (pin "3") (pinfunction "DIG_GND_3") (pintype "passive"))
      (node (ref "J22") (pin "3") (pinfunction "DIG_GND_3") (pintype "passive"))
      (node (ref "J23") (pin "3") (pinfunction "DIG_GND_3") (pintype "passive"))
      (node (ref "J24") (pin "3") (pinfunction "DIG_GND_3") (pintype "passive"))
      (node (ref "J25") (pin "3") (pinfunction "DIG_GND_3") (pintype "passive"))
      (node (ref "J26") (pin "3") (pinfunction "DIG_GND_3") (pintype "passive"))
      (node (ref "P1") (pin "2") (pinfunction "2_2") (pintype "passive"))
      (node (ref "P10") (pin "2") (pinfunction "2_2") (pintype "passive"))
      (node (ref "P11") (pin "2") (pinfunction "2_2") (pintype "passive"))
      (node (ref "P12") (pin "2") (pinfunction "2_2") (pintype "passive"))
      (node (ref "P13") (pin "2") (pinfunction "2_2") (pintype "passive"))
      (node (ref "P14") (pin "2") (pinfunction "2_2") (pintype "passive"))
      (node (ref "P15") (pin "2") (pinfunction "2_2") (pintype "passive"))
      (node (ref "P16") (pin "2") (pinfunction "2_2") (pintype "passive"))
      (node (ref "P17") (pin "2") (pinfunction "2_2") (pintype "passive"))
      (node (ref "P18") (pin "2") (pinfunction "2_2") (pintype "passive"))
      (node (ref "P19") (pin "2") (pinfunction "2_2") (pintype "passive"))
      (node (ref "P2") (pin "2") (pinfunction "2_2") (pintype "passive"))
      (node (ref "P20") (pin "2") (pinfunction "2_2") (pintype "passive"))
      (node (ref "P21") (pin "2") (pinfunction "2_2") (pintype "passive"))
      (node (ref "P22") (pin "2") (pinfunction "2_2") (pintype "passive"))
      (node (ref "P23") (pin "2") (pinfunction "2_2") (pintype "passive"))
      (node (ref "P24") (pin "2") (pinfunction "2_2") (pintype "passive"))
      (node (ref "P3") (pin "2") (pinfunction "2_2") (pintype "passive"))
      (node (ref "P4") (pin "2") (pinfunction "2_2") (pintype "passive"))
      (node (ref "P5") (pin "2") (pinfunction "2_2") (pintype "passive"))
      (node (ref "P6") (pin "2") (pinfunction "2_2") (pintype "passive"))
      (node (ref "P7") (pin "2") (pinfunction "2_2") (pintype "passive"))
      (node (ref "P8") (pin "2") (pinfunction "2_2") (pintype "passive"))
      (node (ref "P9") (pin "2") (pinfunction "2_2") (pintype "passive"))
      (node (ref "U1") (pin "2") (pinfunction "-Ctrll_2") (pintype "passive"))
      (node (ref "U10") (pin "2") (pinfunction "-Ctrll_2") (pintype "passive"))
      (node (ref "U11") (pin "2") (pinfunction "-Ctrll_2") (pintype "passive"))
      (node (ref "U12") (pin "2") (pinfunction "-Ctrll_2") (pintype "passive"))
      (node (ref "U13") (pin "2") (pinfunction "-Ctrll_2") (pintype "passive"))
      (node (ref "U14") (pin "2") (pinfunction "-Ctrll_2") (pintype "passive"))
      (node (ref "U15") (pin "2") (pinfunction "-Ctrll_2") (pintype "passive"))
      (node (ref "U16") (pin "2") (pinfunction "-Ctrll_2") (pintype "passive"))
      (node (ref "U17") (pin "2") (pinfunction "-Ctrll_2") (pintype "passive"))
      (node (ref "U18") (pin "2") (pinfunction "-Ctrll_2") (pintype "passive"))
      (node (ref "U19") (pin "2") (pinfunction "-Ctrll_2") (pintype "passive"))
      (node (ref "U2") (pin "2") (pinfunction "-Ctrll_2") (pintype "passive"))
      (node (ref "U20") (pin "2") (pinfunction "-Ctrll_2") (pintype "passive"))
      (node (ref "U21") (pin "2") (pinfunction "-Ctrll_2") (pintype "passive"))
      (node (ref "U22") (pin "2") (pinfunction "-Ctrll_2") (pintype "passive"))
      (node (ref "U23") (pin "2") (pinfunction "-Ctrll_2") (pintype "passive"))
      (node (ref "U24") (pin "2") (pinfunction "-Ctrll_2") (pintype "passive"))
      (node (ref "U3") (pin "2") (pinfunction "-Ctrll_2") (pintype "passive"))
      (node (ref "U4") (pin "2") (pinfunction "-Ctrll_2") (pintype "passive"))
      (node (ref "U5") (pin "2") (pinfunction "-Ctrll_2") (pintype "passive"))
      (node (ref "U6") (pin "2") (pinfunction "-Ctrll_2") (pintype "passive"))
      (node (ref "U7") (pin "2") (pinfunction "-Ctrll_2") (pintype "passive"))
      (node (ref "U8") (pin "2") (pinfunction "-Ctrll_2") (pintype "passive"))
      (node (ref "U9") (pin "2") (pinfunction "-Ctrll_2") (pintype "passive"))
    )
  )
)
